# face_board.net
KiCad netlist of a schematic drawn in Altium Designer
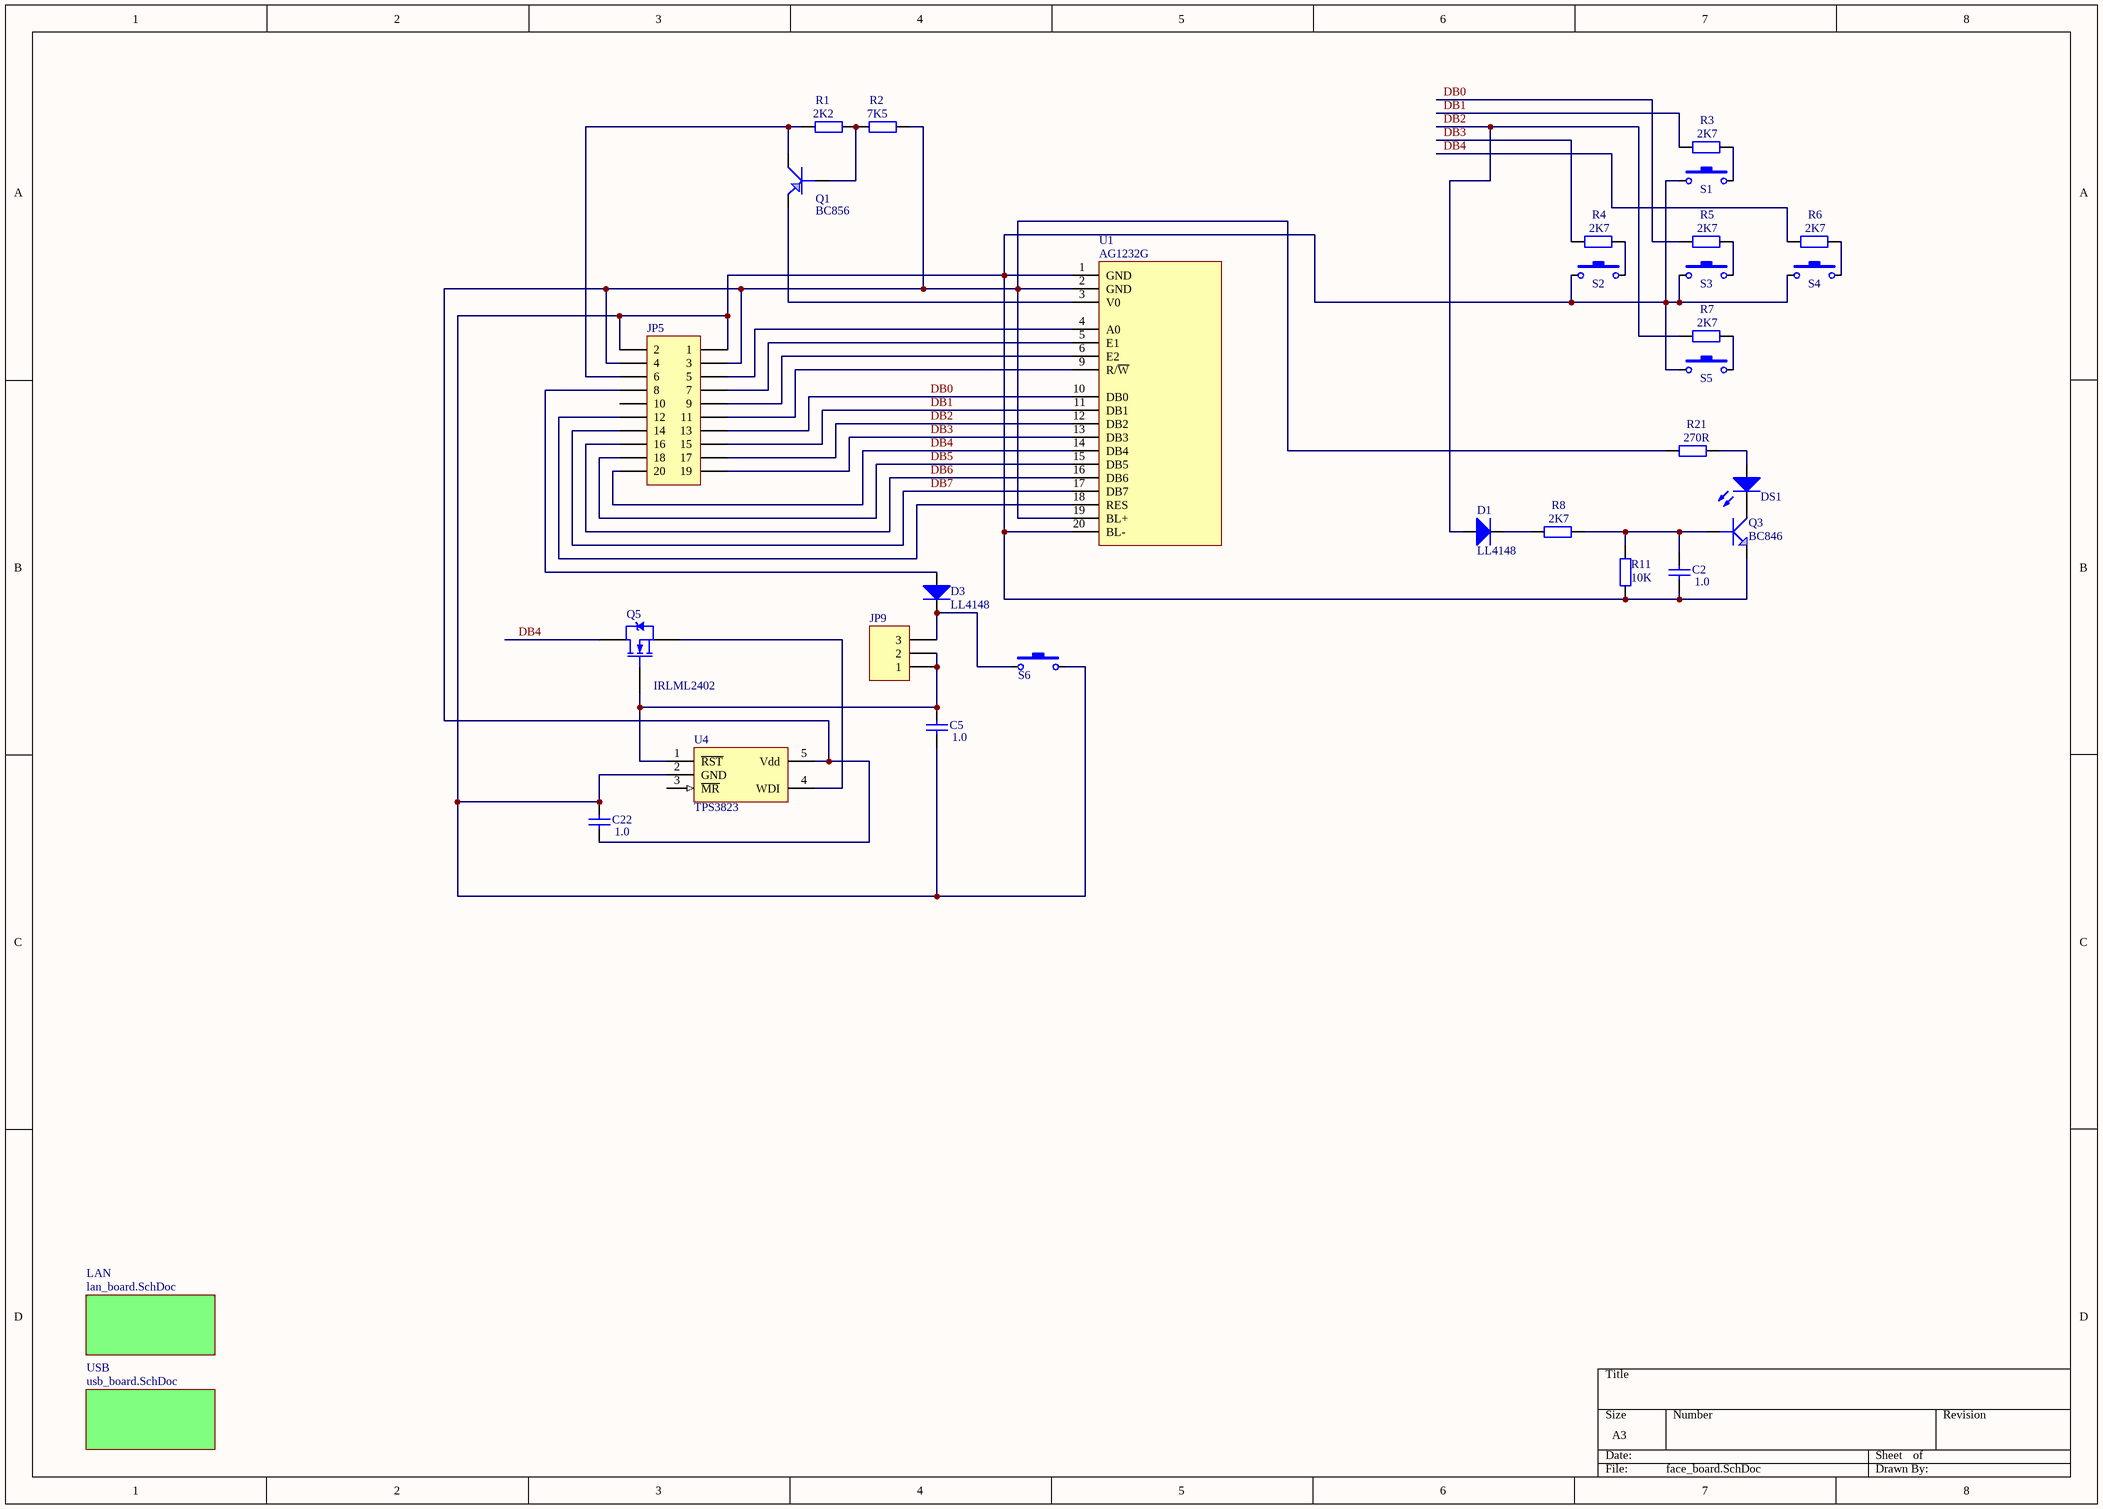
[diagram p0: face_board.SchDoc]

(export (version "E")
  (design (tool "Eeschema 10.0.6"))
  (components
    (comp (ref "C2")
      (value "1.0")
      (footprint "_1206")
      (description "Capacitor")
      (fields (field (name "MANUFACTURER") "Generic Components") (field (name "PUBLISHER") "Altium Limited"))
      (libsource (lib "Miscellaneous Devices") (part "Cap Semi"))
    )
    (comp (ref "C5")
      (value "1.0")
      (footprint "_1206")
      (description "Capacitor")
      (fields (field (name "MANUFACTURER") "Generic Components") (field (name "PUBLISHER") "Altium Limited"))
      (libsource (lib "Miscellaneous Devices") (part "Cap Semi"))
    )
    (comp (ref "C22")
      (value "1.0")
      (footprint "_1206")
      (description "Capacitor")
      (fields (field (name "MANUFACTURER") "Generic Components") (field (name "PUBLISHER") "Altium Limited"))
      (libsource (lib "Miscellaneous Devices") (part "Cap Semi"))
    )
    (comp (ref "D1")
      (value "LL4148")
      (footprint "_1206d")
      (description "Diode")
      (fields (field (name "MANUFACTURER") "Generic Components") (field (name "PUBLISHER") "Altium Limited"))
      (libsource (lib "PAL") (part "Diode"))
    )
    (comp (ref "D3")
      (value "LL4148")
      (footprint "_1206d")
      (description "Diode")
      (fields (field (name "MANUFACTURER") "Generic Components") (field (name "PUBLISHER") "Altium Limited"))
      (libsource (lib "PAL") (part "Diode"))
    )
    (comp (ref "DS1")
      (value "LED0")
      (footprint "el3")
      (description "Typical INFRARED GaAs LED")
      (fields (field (name "MANUFACTURER") "Generic Components") (field (name "PUBLISHER") "Altium Limited"))
      (libsource (lib "PAL") (part "LED0"))
    )
    (comp (ref "JP5")
      (value "PLHD-20")
      (footprint "HDR2X10")
      (description "Header, 10-Pin, Dual row")
      (fields (field (name "MANUFACTURER") "Generic Components") (field (name "PUBLISHER") "Altium Limited"))
      (libsource (lib "Miscellaneous Connectors") (part "Header 10X2"))
    )
    (comp (ref "JP9")
      (value "PLS-3")
      (footprint "HDR1X3")
      (description "Header, 3-Pin")
      (fields (field (name "MANUFACTURER") "Generic Components") (field (name "PUBLISHER") "Altium Limited"))
      (libsource (lib "Miscellaneous Connectors") (part "Header 3"))
    )
    (comp (ref "Q1")
      (value "BC856")
      (footprint "SO-G3")
      (description "Bipolar transistor")
      (libsource (lib "MAIN") (part "GT109"))
    )
    (comp (ref "Q3")
      (value "BC846")
      (footprint "SO-G3")
      (description "Bipolar transistor")
      (libsource (lib "MAIN") (part "GT122"))
    )
    (comp (ref "Q5")
      (value "IRLML2402")
      (footprint "SO-G3")
      (description "HEXFET Power MOSFET")
      (fields
        (field (name "MANUFACTURER") "International Rectifier")
        (field (name "ALTIUM_VALUE") "IRLML2402")
        (field (name "PUBLISHER") "Altium Limited")
      )
      (libsource (lib "IR Discrete MOSFET") (part "IRLML2402"))
    )
    (comp (ref "R1")
      (value "2K2")
      (footprint "_1206")
      (description "Resistor")
      (fields (field (name "MANUFACTURER") "Generic Components") (field (name "PUBLISHER") "Altium Limited"))
      (libsource (lib "Miscellaneous Devices") (part "Res2"))
    )
    (comp (ref "R2")
      (value "7K5")
      (footprint "_1206")
      (description "Resistor")
      (fields (field (name "MANUFACTURER") "Generic Components") (field (name "PUBLISHER") "Altium Limited"))
      (libsource (lib "Miscellaneous Devices") (part "Res2"))
    )
    (comp (ref "R3")
      (value "2K7")
      (footprint "_1206")
      (description "Resistor")
      (fields (field (name "MANUFACTURER") "Generic Components") (field (name "PUBLISHER") "Altium Limited"))
      (libsource (lib "") (part "Res2_1"))
    )
    (comp (ref "R4")
      (value "2K7")
      (footprint "_1206")
      (description "Resistor")
      (fields (field (name "MANUFACTURER") "Generic Components") (field (name "PUBLISHER") "Altium Limited"))
      (libsource (lib "") (part "Res2_1"))
    )
    (comp (ref "R5")
      (value "2K7")
      (footprint "_1206")
      (description "Resistor")
      (fields (field (name "MANUFACTURER") "Generic Components") (field (name "PUBLISHER") "Altium Limited"))
      (libsource (lib "") (part "Res2_1"))
    )
    (comp (ref "R6")
      (value "2K7")
      (footprint "_1206")
      (description "Resistor")
      (fields (field (name "MANUFACTURER") "Generic Components") (field (name "PUBLISHER") "Altium Limited"))
      (libsource (lib "") (part "Res2_1"))
    )
    (comp (ref "R7")
      (value "2K7")
      (footprint "_1206")
      (description "Resistor")
      (fields (field (name "MANUFACTURER") "Generic Components") (field (name "PUBLISHER") "Altium Limited"))
      (libsource (lib "") (part "Res2_1"))
    )
    (comp (ref "R8")
      (value "2K7")
      (footprint "_1206")
      (description "Resistor")
      (fields (field (name "MANUFACTURER") "Generic Components") (field (name "PUBLISHER") "Altium Limited"))
      (libsource (lib "") (part "Res2_1"))
    )
    (comp (ref "R11")
      (value "10K")
      (footprint "_1206")
      (description "Resistor")
      (fields (field (name "MANUFACTURER") "Generic Components") (field (name "PUBLISHER") "Altium Limited"))
      (libsource (lib "") (part "Res2_2"))
    )
    (comp (ref "R21")
      (value "270R")
      (footprint "_1206")
      (description "Resistor")
      (fields (field (name "MANUFACTURER") "Generic Components") (field (name "PUBLISHER") "Altium Limited"))
      (libsource (lib "") (part "Res2_1"))
    )
    (comp (ref "S1")
      (value "SWT-9")
      (footprint "SWT-9")
      (description "Button")
      (fields (field (name "MANUFACTURER") "Generic Components") (field (name "PUBLISHER") "Altium Limited"))
      (libsource (lib "PAL") (part "SWT-9"))
    )
    (comp (ref "S2")
      (value "SWT-9")
      (footprint "SWT-9")
      (description "Button")
      (fields (field (name "MANUFACTURER") "Generic Components") (field (name "PUBLISHER") "Altium Limited"))
      (libsource (lib "PAL") (part "SWT-9"))
    )
    (comp (ref "S3")
      (value "SWT-9")
      (footprint "SWT-9")
      (description "Button")
      (fields (field (name "MANUFACTURER") "Generic Components") (field (name "PUBLISHER") "Altium Limited"))
      (libsource (lib "PAL") (part "SWT-9"))
    )
    (comp (ref "S4")
      (value "SWT-9")
      (footprint "SWT-9")
      (description "Button")
      (fields (field (name "MANUFACTURER") "Generic Components") (field (name "PUBLISHER") "Altium Limited"))
      (libsource (lib "PAL") (part "SWT-9"))
    )
    (comp (ref "S5")
      (value "SWT-9")
      (footprint "SWT-9")
      (description "Button")
      (fields (field (name "MANUFACTURER") "Generic Components") (field (name "PUBLISHER") "Altium Limited"))
      (libsource (lib "PAL") (part "SWT-9"))
    )
    (comp (ref "S6")
      (value "SWT-6")
      (footprint "SWT-6")
      (description "Button")
      (fields (field (name "MANUFACTURER") "Generic Components") (field (name "PUBLISHER") "Altium Limited"))
      (libsource (lib "PAL") (part "SWT-9"))
    )
    (comp (ref "U1")
      (value "AG1232G")
      (footprint "AG1232G")
      (description "LCD")
      (libsource (lib "PAL") (part "AG1232G"))
    )
    (comp (ref "U4")
      (value "TPS3823")
      (footprint "SO-G5/P.95")
      (description "Reset IC")
      (fields
        (field (name "MANUFACTURER") "National Semiconductor")
        (field (name "PUBLISHER") "Altium Limited")
      )
      (libsource (lib "PAL") (part "TPS3823"))
    )
  )
  (nets
    (net (code "1") (name "/DB0") (class "Default")
      (node (ref "JP5") (pin "13") (pinfunction "13_13") (pintype "passive"))
      (node (ref "R5") (pin "2") (pinfunction "2_2") (pintype "passive"))
      (node (ref "U1") (pin "10") (pinfunction "DB0_10") (pintype "passive"))
    )
    (net (code "2") (name "/DB1") (class "Default")
      (node (ref "JP5") (pin "15") (pinfunction "15_15") (pintype "passive"))
      (node (ref "R3") (pin "2") (pinfunction "2_2") (pintype "passive"))
      (node (ref "U1") (pin "11") (pinfunction "DB1_11") (pintype "passive"))
    )
    (net (code "3") (name "/DB2") (class "Default")
      (node (ref "D1") (pin "1") (pinfunction "A_1") (pintype "passive"))
      (node (ref "JP5") (pin "17") (pinfunction "17_17") (pintype "passive"))
      (node (ref "R7") (pin "2") (pinfunction "2_2") (pintype "passive"))
      (node (ref "U1") (pin "12") (pinfunction "DB2_12") (pintype "passive"))
    )
    (net (code "4") (name "/DB3") (class "Default")
      (node (ref "JP5") (pin "19") (pinfunction "19_19") (pintype "passive"))
      (node (ref "R4") (pin "2") (pinfunction "2_2") (pintype "passive"))
      (node (ref "U1") (pin "13") (pinfunction "DB3_13") (pintype "passive"))
    )
    (net (code "5") (name "/DB4") (class "Default")
      (node (ref "JP5") (pin "20") (pinfunction "20_20") (pintype "passive"))
      (node (ref "Q5") (pin "3") (pinfunction "D_3") (pintype "passive"))
      (node (ref "R6") (pin "2") (pinfunction "2_2") (pintype "passive"))
      (node (ref "U1") (pin "14") (pinfunction "DB4_14") (pintype "passive"))
    )
    (net (code "6") (name "/DB5") (class "Default")
      (node (ref "JP5") (pin "18") (pinfunction "18_18") (pintype "passive"))
      (node (ref "U1") (pin "15") (pinfunction "DB5_15") (pintype "passive"))
    )
    (net (code "7") (name "/DB6") (class "Default")
      (node (ref "JP5") (pin "16") (pinfunction "16_16") (pintype "passive"))
      (node (ref "U1") (pin "16") (pinfunction "DB6_16") (pintype "passive"))
    )
    (net (code "8") (name "/DB7") (class "Default")
      (node (ref "JP5") (pin "14") (pinfunction "14_14") (pintype "passive"))
      (node (ref "U1") (pin "17") (pinfunction "DB7_17") (pintype "passive"))
    )
    (net (code "9") (name "Net-(D1-K)") (class "Default")
      (node (ref "D1") (pin "2") (pinfunction "K_2") (pintype "passive"))
      (node (ref "R8") (pin "2") (pinfunction "2_2") (pintype "passive"))
    )
    (net (code "10") (name "Net-(D3-A)") (class "Default")
      (node (ref "D3") (pin "1") (pinfunction "A_1") (pintype "passive"))
      (node (ref "JP5") (pin "8") (pinfunction "8_8") (pintype "passive"))
    )
    (net (code "11") (name "Net-(D3-K)") (class "Default")
      (node (ref "D3") (pin "2") (pinfunction "K_2") (pintype "passive"))
      (node (ref "JP9") (pin "3") (pinfunction "3_3") (pintype "passive"))
      (node (ref "S6") (pin "1") (pinfunction "1_1") (pintype "passive"))
    )
    (net (code "12") (name "Net-(DS1-A)") (class "Default")
      (node (ref "DS1") (pin "1") (pinfunction "A_1") (pintype "passive"))
      (node (ref "R21") (pin "1") (pinfunction "1_1") (pintype "passive"))
    )
    (net (code "13") (name "Net-(DS1-K)") (class "Default")
      (node (ref "DS1") (pin "2") (pinfunction "K_2") (pintype "passive"))
      (node (ref "Q3") (pin "3") (pinfunction "C_3") (pintype "passive"))
    )
    (net (code "14") (name "Net-(Q1-B)") (class "Default")
      (node (ref "Q1") (pin "1") (pinfunction "B_1") (pintype "passive"))
      (node (ref "R1") (pin "2") (pinfunction "2_2") (pintype "passive"))
      (node (ref "R2") (pin "1") (pinfunction "1_1") (pintype "passive"))
    )
    (net (code "15") (name "Net-(Q1-C)") (class "Default")
      (node (ref "JP5") (pin "6") (pinfunction "6_6") (pintype "passive"))
      (node (ref "Q1") (pin "3") (pinfunction "C_3") (pintype "passive"))
      (node (ref "R1") (pin "1") (pinfunction "1_1") (pintype "passive"))
    )
    (net (code "16") (name "Net-(Q1-E)") (class "Default")
      (node (ref "Q1") (pin "2") (pinfunction "E_2") (pintype "passive"))
      (node (ref "U1") (pin "3") (pinfunction "V0_3") (pintype "passive"))
    )
    (net (code "17") (name "Net-(Q3-B)") (class "Default")
      (node (ref "C2") (pin "2") (pinfunction "2_2") (pintype "passive"))
      (node (ref "Q3") (pin "1") (pinfunction "B_1") (pintype "passive"))
      (node (ref "R11") (pin "1") (pinfunction "1_1") (pintype "passive"))
      (node (ref "R8") (pin "1") (pinfunction "1_1") (pintype "passive"))
    )
    (net (code "18") (name "Net-(Q3-E)") (class "Default")
      (node (ref "C2") (pin "1") (pinfunction "1_1") (pintype "passive"))
      (node (ref "C22") (pin "2") (pinfunction "2_2") (pintype "passive"))
      (node (ref "C5") (pin "1") (pinfunction "1_1") (pintype "passive"))
      (node (ref "JP5") (pin "1") (pinfunction "1_1") (pintype "passive"))
      (node (ref "JP5") (pin "2") (pinfunction "2_2") (pintype "passive"))
      (node (ref "Q3") (pin "2") (pinfunction "E_2") (pintype "passive"))
      (node (ref "R11") (pin "2") (pinfunction "2_2") (pintype "passive"))
      (node (ref "S1") (pin "1") (pinfunction "1_1") (pintype "passive"))
      (node (ref "S2") (pin "1") (pinfunction "1_1") (pintype "passive"))
      (node (ref "S3") (pin "1") (pinfunction "1_1") (pintype "passive"))
      (node (ref "S4") (pin "1") (pinfunction "1_1") (pintype "passive"))
      (node (ref "S5") (pin "1") (pinfunction "1_1") (pintype "passive"))
      (node (ref "S6") (pin "2") (pinfunction "2_2") (pintype "passive"))
      (node (ref "U1") (pin "1") (pinfunction "GND_1") (pintype "passive"))
      (node (ref "U1") (pin "20") (pinfunction "BL-_20") (pintype "passive"))
      (node (ref "U4") (pin "2") (pinfunction "GND_2") (pintype "power_in"))
    )
    (net (code "19") (name "Net-(Q5-G)") (class "Default")
      (node (ref "C5") (pin "2") (pinfunction "2_2") (pintype "passive"))
      (node (ref "JP9") (pin "1") (pinfunction "1_1") (pintype "passive"))
      (node (ref "JP9") (pin "2") (pinfunction "2_2") (pintype "passive"))
      (node (ref "Q5") (pin "1") (pinfunction "G_1") (pintype "passive"))
      (node (ref "U4") (pin "1") (pinfunction "~{RST}_1") (pintype "power_in"))
    )
    (net (code "20") (name "Net-(Q5-S)") (class "Default")
      (node (ref "Q5") (pin "2") (pinfunction "S_2") (pintype "passive"))
      (node (ref "U4") (pin "4") (pinfunction "WDI_4") (pintype "passive"))
    )
    (net (code "21") (name "Net-(R3-Pad1)") (class "Default")
      (node (ref "R3") (pin "1") (pinfunction "1_1") (pintype "passive"))
      (node (ref "S1") (pin "2") (pinfunction "2_2") (pintype "passive"))
    )
    (net (code "22") (name "Net-(R4-Pad1)") (class "Default")
      (node (ref "R4") (pin "1") (pinfunction "1_1") (pintype "passive"))
      (node (ref "S2") (pin "2") (pinfunction "2_2") (pintype "passive"))
    )
    (net (code "23") (name "Net-(R5-Pad1)") (class "Default")
      (node (ref "R5") (pin "1") (pinfunction "1_1") (pintype "passive"))
      (node (ref "S3") (pin "2") (pinfunction "2_2") (pintype "passive"))
    )
    (net (code "24") (name "Net-(R6-Pad1)") (class "Default")
      (node (ref "R6") (pin "1") (pinfunction "1_1") (pintype "passive"))
      (node (ref "S4") (pin "2") (pinfunction "2_2") (pintype "passive"))
    )
    (net (code "25") (name "Net-(R7-Pad1)") (class "Default")
      (node (ref "R7") (pin "1") (pinfunction "1_1") (pintype "passive"))
      (node (ref "S5") (pin "2") (pinfunction "2_2") (pintype "passive"))
    )
    (net (code "26") (name "Net-(U1-A0)") (class "Default")
      (node (ref "JP5") (pin "5") (pinfunction "5_5") (pintype "passive"))
      (node (ref "U1") (pin "4") (pinfunction "A0_4") (pintype "passive"))
    )
    (net (code "27") (name "Net-(U1-BL+)") (class "Default")
      (node (ref "C22") (pin "1") (pinfunction "1_1") (pintype "passive"))
      (node (ref "JP5") (pin "3") (pinfunction "3_3") (pintype "passive"))
      (node (ref "JP5") (pin "4") (pinfunction "4_4") (pintype "passive"))
      (node (ref "R2") (pin "2") (pinfunction "2_2") (pintype "passive"))
      (node (ref "R21") (pin "2") (pinfunction "2_2") (pintype "passive"))
      (node (ref "U1") (pin "19") (pinfunction "BL+_19") (pintype "passive"))
      (node (ref "U1") (pin "2") (pinfunction "GND_2") (pintype "passive"))
      (node (ref "U4") (pin "5") (pinfunction "Vdd_5") (pintype "power_in"))
    )
    (net (code "28") (name "Net-(U1-E1)") (class "Default")
      (node (ref "JP5") (pin "7") (pinfunction "7_7") (pintype "passive"))
      (node (ref "U1") (pin "5") (pinfunction "E1_5") (pintype "passive"))
    )
    (net (code "29") (name "Net-(U1-E2)") (class "Default")
      (node (ref "JP5") (pin "9") (pinfunction "9_9") (pintype "passive"))
      (node (ref "U1") (pin "6") (pinfunction "E2_6") (pintype "passive"))
    )
    (net (code "30") (name "Net-(U1-RES)") (class "Default")
      (node (ref "JP5") (pin "12") (pinfunction "12_12") (pintype "passive"))
      (node (ref "U1") (pin "18") (pinfunction "RES_18") (pintype "passive"))
    )
    (net (code "31") (name "Net-(U1-R{slash}~{W})") (class "Default")
      (node (ref "JP5") (pin "11") (pinfunction "11_11") (pintype "passive"))
      (node (ref "U1") (pin "9") (pinfunction "R/~{W}_9") (pintype "passive"))
    )
    (net (code "32") (name "unconnected-(JP5-Pad10)") (class "Default")
      (node (ref "JP5") (pin "10") (pinfunction "10_10") (pintype "passive"))
    )
    (net (code "33") (name "unconnected-(U4-~{MR}-Pad3)") (class "Default")
      (node (ref "U4") (pin "3") (pinfunction "~{MR}_3") (pintype "input"))
    )
  )
)
